# avr_apple_remote.net
KiCad netlist of a schematic drawn in EAGLE
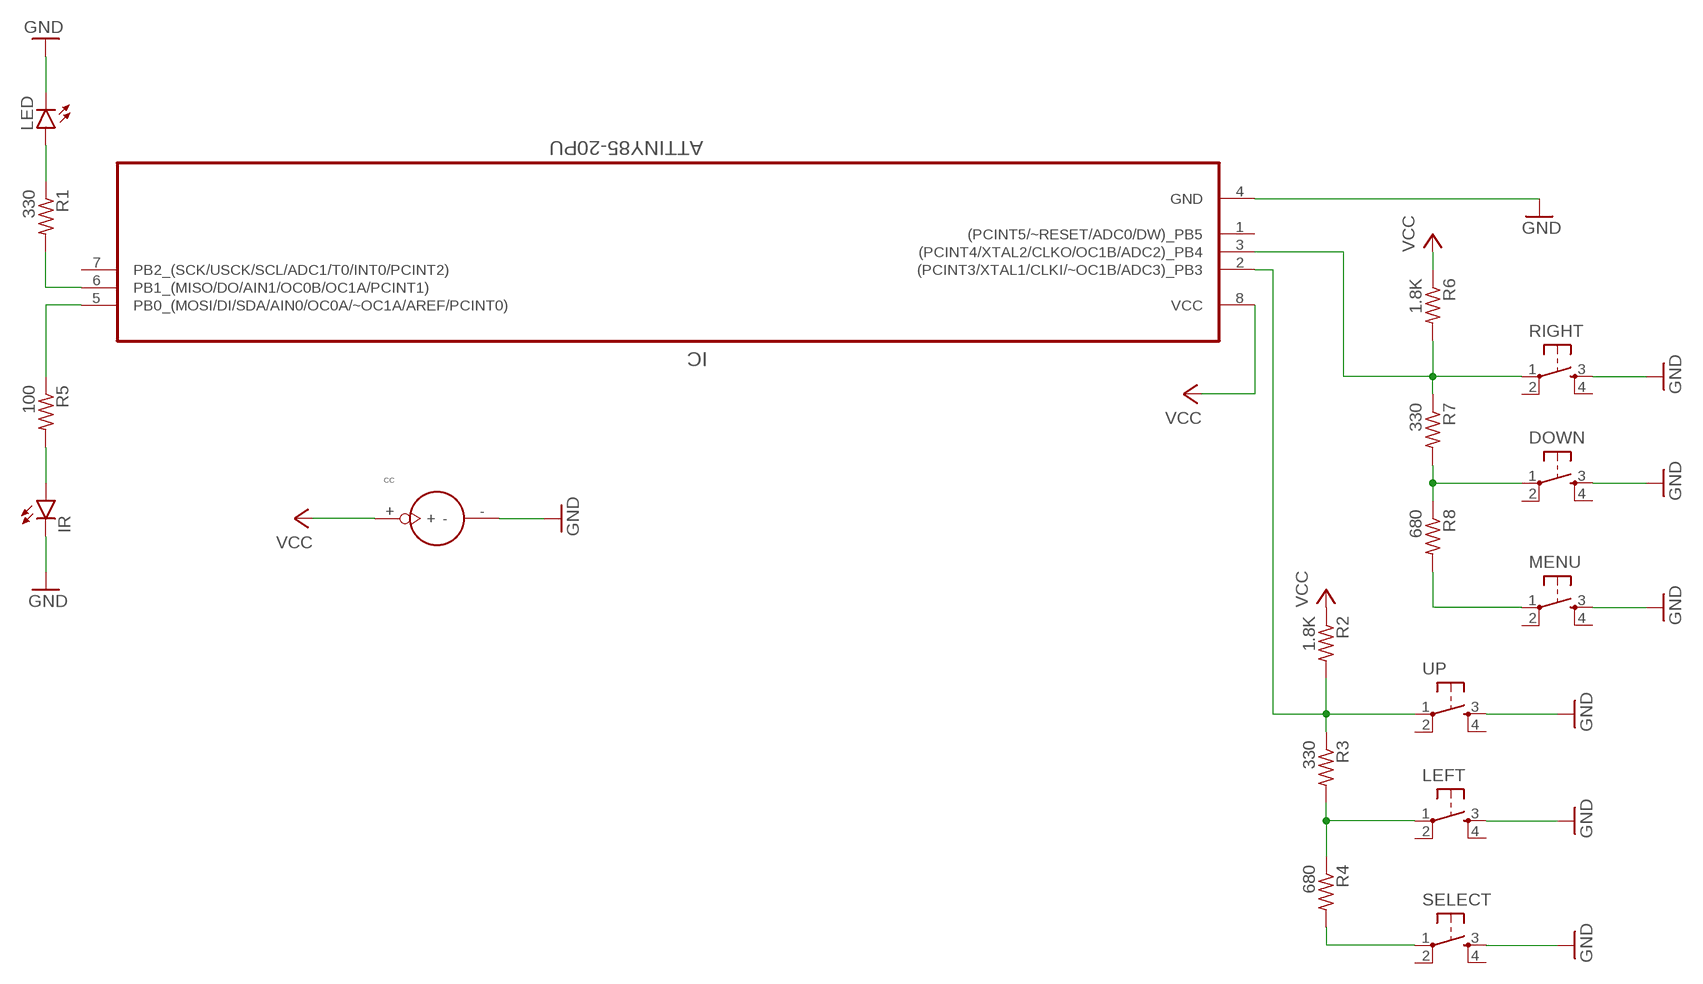
[diagram p0: schematic, sheet 1]

(export (version "E")
  (design (tool "Eeschema 10.0.6"))
  (components
    (comp (ref "CC")
      (value "BATTERY_1236_C")
      (footprint "eagle-import:BATTERY_1236_C")
      (libsource (lib "eagle-import") (part "BATTERY_1236_C"))
    )
    (comp (ref "DOWN")
      (value "TACTILE-SWITCH-PTH")
      (footprint "eagle-import:TAC-SWITCH-PTH")
      (libsource (lib "eagle-import") (part "TACTILE-SWITCH-PTH"))
    )
    (comp (ref "IC")
      (value "ATTINY85-20PU")
      (footprint "eagle-import:DIP254P762X533-8")
      (libsource (lib "eagle-import") (part "ATTINY85-20PU"))
    )
    (comp (ref "IR")
      (value "LED5MM")
      (footprint "eagle-import:LED5MM")
      (libsource (lib "eagle-import") (part "LED5MM"))
    )
    (comp (ref "LED")
      (value "LED5MM")
      (footprint "eagle-import:LED5MM")
      (libsource (lib "eagle-import") (part "LED5MM"))
    )
    (comp (ref "LEFT")
      (value "TACTILE-SWITCH-PTH")
      (footprint "eagle-import:TAC-SWITCH-PTH")
      (libsource (lib "eagle-import") (part "TACTILE-SWITCH-PTH"))
    )
    (comp (ref "MENU")
      (value "TACTILE-SWITCH-PTH")
      (footprint "eagle-import:TAC-SWITCH-PTH")
      (libsource (lib "eagle-import") (part "TACTILE-SWITCH-PTH"))
    )
    (comp (ref "R1")
      (value "330")
      (footprint "eagle-import:0207_10")
      (libsource (lib "eagle-import") (part "R-US_0207/10"))
    )
    (comp (ref "R2")
      (value "1.8K")
      (footprint "eagle-import:0207_10")
      (libsource (lib "eagle-import") (part "R-US_0207/10"))
    )
    (comp (ref "R3")
      (value "330")
      (footprint "eagle-import:0207_10")
      (libsource (lib "eagle-import") (part "R-US_0207/10"))
    )
    (comp (ref "R4")
      (value "680")
      (footprint "eagle-import:0207_10")
      (libsource (lib "eagle-import") (part "R-US_0207/10"))
    )
    (comp (ref "R5")
      (value "100")
      (footprint "eagle-import:0207_10")
      (libsource (lib "eagle-import") (part "R-US_0207/10"))
    )
    (comp (ref "R6")
      (value "1.8K")
      (footprint "eagle-import:0207_10")
      (libsource (lib "eagle-import") (part "R-US_0207/10"))
    )
    (comp (ref "R7")
      (value "330")
      (footprint "eagle-import:0207_10")
      (libsource (lib "eagle-import") (part "R-US_0207/10"))
    )
    (comp (ref "R8")
      (value "680")
      (footprint "eagle-import:0207_10")
      (libsource (lib "eagle-import") (part "R-US_0207/10"))
    )
    (comp (ref "RIGHT")
      (value "TACTILE-SWITCH-PTH")
      (footprint "eagle-import:TAC-SWITCH-PTH")
      (libsource (lib "eagle-import") (part "TACTILE-SWITCH-PTH"))
    )
    (comp (ref "SELECT")
      (value "TACTILE-SWITCH-PTH")
      (footprint "eagle-import:TAC-SWITCH-PTH")
      (libsource (lib "eagle-import") (part "TACTILE-SWITCH-PTH"))
    )
    (comp (ref "UP")
      (value "TACTILE-SWITCH-PTH")
      (footprint "eagle-import:TAC-SWITCH-PTH")
      (libsource (lib "eagle-import") (part "TACTILE-SWITCH-PTH"))
    )
  )
  (nets
    (net (code "1") (name "GND") (class "Default")
      (node (ref "CC") (pin "-") (pinfunction "-_-") (pintype "bidirectional"))
      (node (ref "DOWN") (pin "3") (pinfunction "3_3") (pintype "passive"))
      (node (ref "IC") (pin "4") (pinfunction "GND_4") (pintype "passive"))
      (node (ref "IR") (pin "K") (pinfunction "C_K") (pintype "passive"))
      (node (ref "LED") (pin "K") (pinfunction "C_K") (pintype "passive"))
      (node (ref "LEFT") (pin "3") (pinfunction "3_3") (pintype "passive"))
      (node (ref "MENU") (pin "3") (pinfunction "3_3") (pintype "passive"))
      (node (ref "RIGHT") (pin "3") (pinfunction "3_3") (pintype "passive"))
      (node (ref "SELECT") (pin "3") (pinfunction "3_3") (pintype "passive"))
      (node (ref "UP") (pin "3") (pinfunction "3_3") (pintype "passive"))
    )
    (net (code "2") (name "Net-(DOWN-Pad1)") (class "Default")
      (node (ref "DOWN") (pin "1") (pinfunction "1_1") (pintype "passive"))
      (node (ref "R7") (pin "2") (pinfunction "2_2") (pintype "passive"))
      (node (ref "R8") (pin "1") (pinfunction "1_1") (pintype "passive"))
    )
    (net (code "3") (name "Net-(IC-(PCINT3{slash}XTAL1{slash}CLKI{slash}~{OC1B{slash}ADC3})_PB3)") (class "Default")
      (node (ref "IC") (pin "2") (pinfunction "(PCINT3/XTAL1/CLKI/~{OC1B/ADC3})_PB3_2") (pintype "bidirectional"))
      (node (ref "R2") (pin "2") (pinfunction "2_2") (pintype "passive"))
      (node (ref "R3") (pin "1") (pinfunction "1_1") (pintype "passive"))
      (node (ref "UP") (pin "1") (pinfunction "1_1") (pintype "passive"))
    )
    (net (code "4") (name "Net-(IC-(PCINT4{slash}XTAL2{slash}CLKO{slash}OC1B{slash}ADC2)_PB4)") (class "Default")
      (node (ref "IC") (pin "3") (pinfunction "(PCINT4/XTAL2/CLKO/OC1B/ADC2)_PB4_3") (pintype "bidirectional"))
      (node (ref "R6") (pin "2") (pinfunction "2_2") (pintype "passive"))
      (node (ref "R7") (pin "1") (pinfunction "1_1") (pintype "passive"))
      (node (ref "RIGHT") (pin "1") (pinfunction "1_1") (pintype "passive"))
    )
    (net (code "5") (name "Net-(IC-PB0_(MOSI{slash}DI{slash}SDA{slash}AIN0{slash}OC0A{slash}~{OC1A{slash}AREF{slash}PCINT0}))") (class "Default")
      (node (ref "IC") (pin "5") (pinfunction "PB0_(MOSI/DI/SDA/AIN0/OC0A/~{OC1A/AREF/PCINT0})_5") (pintype "bidirectional"))
      (node (ref "R5") (pin "1") (pinfunction "1_1") (pintype "passive"))
    )
    (net (code "6") (name "Net-(IC-PB1_(MISO{slash}DO{slash}AIN1{slash}OC0B{slash}OC1A{slash}PCINT1))") (class "Default")
      (node (ref "IC") (pin "6") (pinfunction "PB1_(MISO/DO/AIN1/OC0B/OC1A/PCINT1)_6") (pintype "bidirectional"))
      (node (ref "R1") (pin "2") (pinfunction "2_2") (pintype "passive"))
    )
    (net (code "7") (name "Net-(IR-PadA)") (class "Default")
      (node (ref "IR") (pin "A") (pinfunction "A_A") (pintype "passive"))
      (node (ref "R5") (pin "2") (pinfunction "2_2") (pintype "passive"))
    )
    (net (code "8") (name "Net-(LED-PadA)") (class "Default")
      (node (ref "LED") (pin "A") (pinfunction "A_A") (pintype "passive"))
      (node (ref "R1") (pin "1") (pinfunction "1_1") (pintype "passive"))
    )
    (net (code "9") (name "Net-(LEFT-Pad1)") (class "Default")
      (node (ref "LEFT") (pin "1") (pinfunction "1_1") (pintype "passive"))
      (node (ref "R3") (pin "2") (pinfunction "2_2") (pintype "passive"))
      (node (ref "R4") (pin "1") (pinfunction "1_1") (pintype "passive"))
    )
    (net (code "10") (name "Net-(MENU-Pad1)") (class "Default")
      (node (ref "MENU") (pin "1") (pinfunction "1_1") (pintype "passive"))
      (node (ref "R8") (pin "2") (pinfunction "2_2") (pintype "passive"))
    )
    (net (code "11") (name "Net-(R4-Pad2)") (class "Default")
      (node (ref "R4") (pin "2") (pinfunction "2_2") (pintype "passive"))
      (node (ref "SELECT") (pin "1") (pinfunction "1_1") (pintype "passive"))
    )
    (net (code "12") (name "VCC") (class "Default")
      (node (ref "CC") (pin "+") (pinfunction "+_+") (pintype "bidirectional"))
      (node (ref "IC") (pin "8") (pinfunction "VCC_8") (pintype "power_in"))
      (node (ref "R2") (pin "1") (pinfunction "1_1") (pintype "passive"))
      (node (ref "R6") (pin "1") (pinfunction "1_1") (pintype "passive"))
    )
    (net (code "13") (name "unconnected-(DOWN-Pad2)") (class "Default")
      (node (ref "DOWN") (pin "2") (pinfunction "2_2") (pintype "passive"))
    )
    (net (code "14") (name "unconnected-(DOWN-Pad4)") (class "Default")
      (node (ref "DOWN") (pin "4") (pinfunction "4_4") (pintype "passive"))
    )
    (net (code "15") (name "unconnected-(IC-(PCINT5{slash}~{RESET{slash}ADC0{slash}DW})_PB5-Pad1)") (class "Default")
      (node (ref "IC") (pin "1") (pinfunction "(PCINT5/~{RESET/ADC0/DW})_PB5_1") (pintype "bidirectional"))
    )
    (net (code "16") (name "unconnected-(IC-PB2_(SCK{slash}USCK{slash}SCL{slash}ADC1{slash}T0{slash}INT0{slash}PCINT2)-Pad7)") (class "Default")
      (node (ref "IC") (pin "7") (pinfunction "PB2_(SCK/USCK/SCL/ADC1/T0/INT0/PCINT2)_7") (pintype "bidirectional"))
    )
    (net (code "17") (name "unconnected-(LEFT-Pad2)") (class "Default")
      (node (ref "LEFT") (pin "2") (pinfunction "2_2") (pintype "passive"))
    )
    (net (code "18") (name "unconnected-(LEFT-Pad4)") (class "Default")
      (node (ref "LEFT") (pin "4") (pinfunction "4_4") (pintype "passive"))
    )
    (net (code "19") (name "unconnected-(MENU-Pad2)") (class "Default")
      (node (ref "MENU") (pin "2") (pinfunction "2_2") (pintype "passive"))
    )
    (net (code "20") (name "unconnected-(MENU-Pad4)") (class "Default")
      (node (ref "MENU") (pin "4") (pinfunction "4_4") (pintype "passive"))
    )
    (net (code "21") (name "unconnected-(RIGHT-Pad2)") (class "Default")
      (node (ref "RIGHT") (pin "2") (pinfunction "2_2") (pintype "passive"))
    )
    (net (code "22") (name "unconnected-(RIGHT-Pad4)") (class "Default")
      (node (ref "RIGHT") (pin "4") (pinfunction "4_4") (pintype "passive"))
    )
    (net (code "23") (name "unconnected-(SELECT-Pad2)") (class "Default")
      (node (ref "SELECT") (pin "2") (pinfunction "2_2") (pintype "passive"))
    )
    (net (code "24") (name "unconnected-(SELECT-Pad4)") (class "Default")
      (node (ref "SELECT") (pin "4") (pinfunction "4_4") (pintype "passive"))
    )
    (net (code "25") (name "unconnected-(UP-Pad2)") (class "Default")
      (node (ref "UP") (pin "2") (pinfunction "2_2") (pintype "passive"))
    )
    (net (code "26") (name "unconnected-(UP-Pad4)") (class "Default")
      (node (ref "UP") (pin "4") (pinfunction "4_4") (pintype "passive"))
    )
  )
)
